# Peripherals.net
KiCad netlist of a schematic drawn in Altium Designer
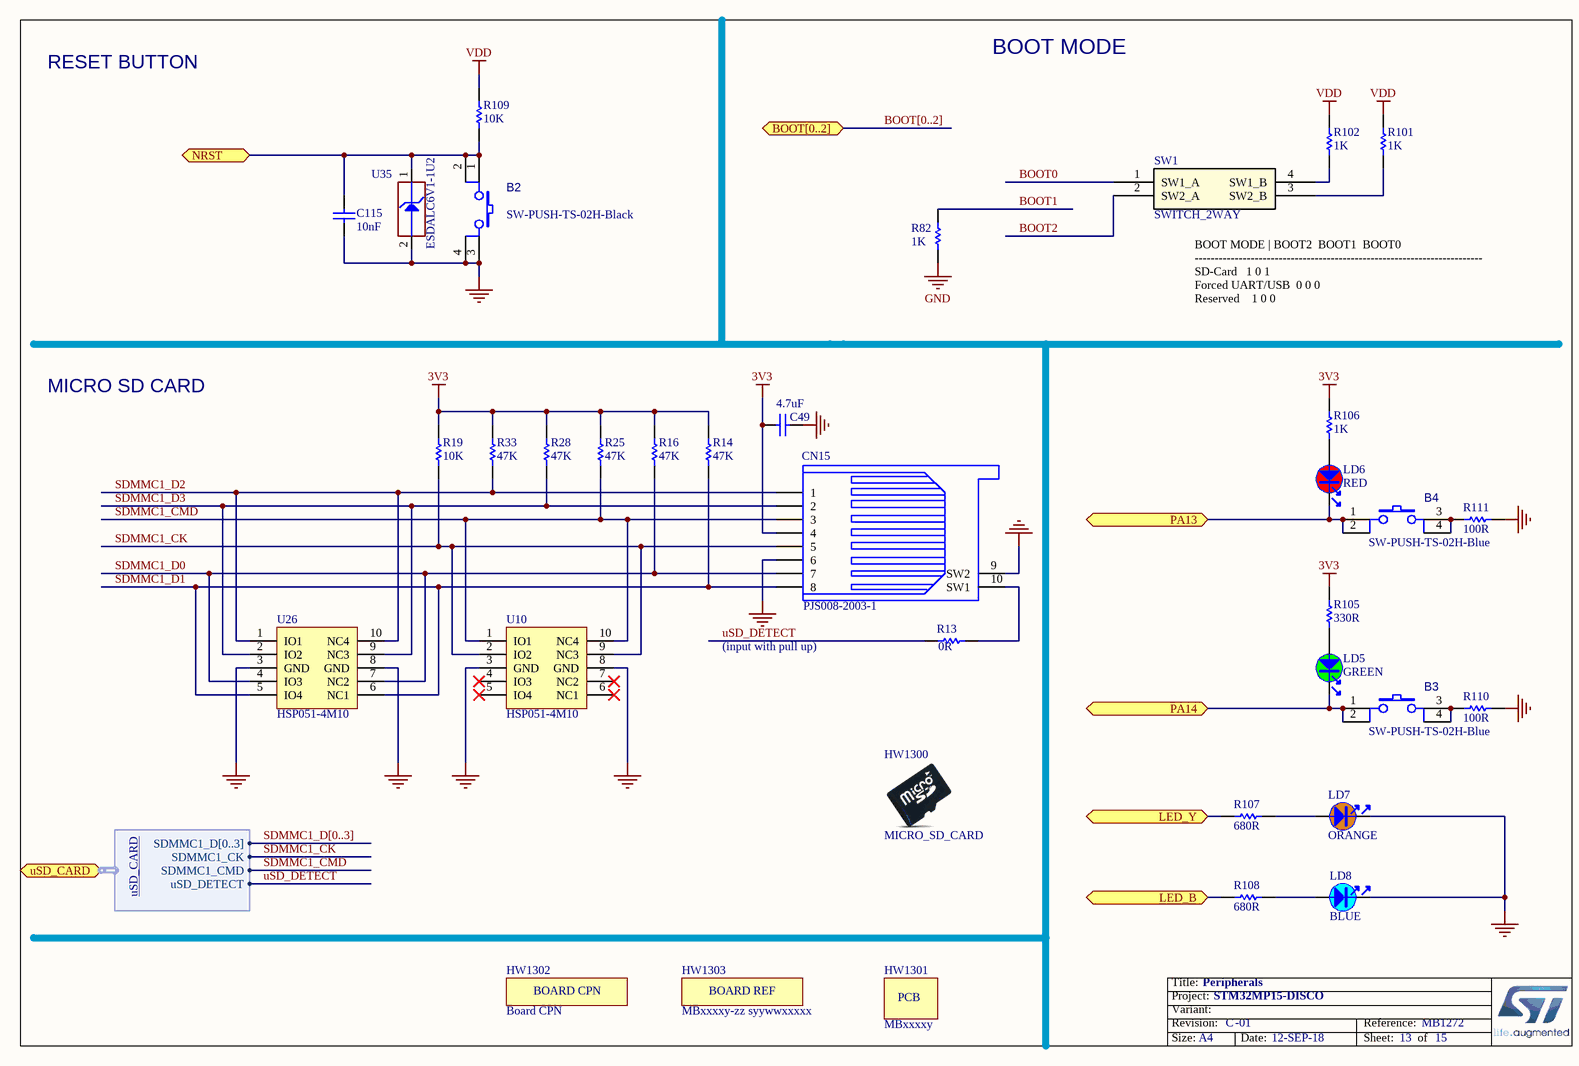
[diagram p0: Peripherals.SchDoc]

(export (version "E")
  (design (tool "Eeschema 10.0.6"))
  (components
    (comp (ref "B2")
      (value "SW-PUSH-TS-02H-Black")
      (footprint "SWI_JIUBABA_C-TS-02H-2-5-K-V-T_R_BLACK")
      (description "Switch HW SMD black")
      (fields
        (field (name "INTERNAL_PART_NUMBER") "MCD-00171")
        (field (name "MANUFACTURER_PART_NUMBER") "C-TS-02H-2.5-K-V-T/R BLACK")
        (field (name "PROVIDED_BY") "SUBCO")
      )
      (libsource (lib "MCD_PARTS_database") (part "SW-PUSH-TS-02H-Black"))
    )
    (comp (ref "B3")
      (value "SW-PUSH-TS-02H-Blue")
      (footprint "SWI_JIUBABA_C-TS-02H-2-5-B-V-T_R_BLUE")
      (description "Switch HW SMD blue")
      (fields
        (field (name "INTERNAL_PART_NUMBER") "MCD-00172")
        (field (name "MANUFACTURER_PART_NUMBER") "C-TS-02H-2.5-B-V-T/R BLUE")
        (field (name "PROVIDED_BY") "SUBCO")
      )
      (libsource (lib "MCD_PARTS_database") (part "SW-PUSH-TS-02H-Blue"))
    )
    (comp (ref "B4")
      (value "SW-PUSH-TS-02H-Blue")
      (footprint "SWI_JIUBABA_C-TS-02H-2-5-B-V-T_R_BLUE")
      (description "Switch HW SMD blue")
      (fields
        (field (name "INTERNAL_PART_NUMBER") "MCD-00172")
        (field (name "MANUFACTURER_PART_NUMBER") "C-TS-02H-2.5-B-V-T/R BLUE")
        (field (name "PROVIDED_BY") "SUBCO")
      )
      (libsource (lib "MCD_PARTS_database") (part "SW-PUSH-TS-02H-Blue"))
    )
    (comp (ref "C49")
      (value "4.7uF")
      (footprint "C0402")
      (description "Capacitor, MLCC, 4.7uF, 6V3, X5R, 20%, 0402, T=0,5mm")
      (fields
        (field (name "INTERNAL_PART_NUMBER") "MCD-01356")
        (field (name "MANUFACTURER_PART_NUMBER") "GRM155R60J475ME47")
        (field (name "PROVIDED_BY") "SUBCO")
      )
      (libsource (lib "MCD_PARTS_database") (part "Capacitor"))
    )
    (comp (ref "C115")
      (value "10nF")
      (footprint "C0402")
      (description "Capacitor, MLCC, 10nF, 16V, X7R, 10%, 0402, T=0.5mm")
      (fields
        (field (name "INTERNAL_PART_NUMBER") "MCD-00011")
        (field (name "MANUFACTURER_PART_NUMBER") "CC0402KRX7R7BB103")
        (field (name "PROVIDED_BY") "SUBCO")
      )
      (libsource (lib "MCD_PARTS_database") (part "Capacitor"))
    )
    (comp (ref "CN15")
      (value "PJS008-2003-1")
      (footprint "CON_MICROSD_YAMAICHI_PJS008-2003-0")
      (description "MicroSD Card Conn, Reversed-Type, Mnt Push-Push")
      (fields
        (field (name "INTERNAL_PART_NUMBER") "MCD-00023")
        (field (name "MANUFACTURER") "YAMAICHI")
        (field (name "PROVIDED_BY") "SUBCO")
      )
      (libsource (lib "MCD_PARTS_database") (part "microSD-PJS008-2003"))
    )
    (comp (ref "HW1300")
      (value "MICRO_SD_CARD")
      (description "MICRO_SD_CARD Standard min 4GB")
      (fields
        (field (name "INTERNAL_PART_NUMBER") "MCD-01200")
        (field (name "MANUFACTURER_PART_NUMBER") "SD_CARD")
        (field (name "PROVIDED_BY") "SUBCO")
      )
      (libsource (lib "MCD_PARTS_database") (part "Micro_SD_card"))
    )
    (comp (ref "HW1301")
      (value "MBxxxxy")
      (description "PCB, xxxx for PCB ref, Y for revision")
      (fields
        (field (name "INTERNAL_PART_NUMBER") "MCD-00216")
        (field (name "MANUFACTURER") "n/a")
        (field (name "PROVIDED_BY") "SUBCO")
      )
      (libsource (lib "MCD_PARTS_database") (part "PCB"))
    )
    (comp (ref "HW1302")
      (value "Board CPN")
      (footprint "STICKER_BOARD-CPN_25X5")
      (description "Sticker to mention board CPN code")
      (fields
        (field (name "INTERNAL_PART_NUMBER") "MCD-00547")
        (field (name "MANUFACTURER_PART_NUMBER") "n/a")
        (field (name "PROVIDED_BY") "SUBCO")
      )
      (libsource (lib "MCD_PARTS_database") (part "STICKER_BOARD_CPN"))
    )
    (comp (ref "HW1303")
      (value "MBxxxxy-zz syywwxxxxx")
      (footprint "STICKER_BOARD-REF_25X5")
      (description "Sticker to mention board reference + serial number")
      (fields
        (field (name "INTERNAL_PART_NUMBER") "MCD-00235")
        (field (name "MANUFACTURER_PART_NUMBER") "n/a")
        (field (name "PROVIDED_BY") "SUBCO")
      )
      (libsource (lib "MCD_PARTS_database") (part "STICKER_BOARD_REF"))
    )
    (comp (ref "LD5")
      (value "GREEN")
      (footprint "LED_0603_GREEN")
      (description "LED, Green, 0603")
      (fields
        (field (name "INTERNAL_PART_NUMBER") "MCD-00050")
        (field (name "MANUFACTURER_PART_NUMBER") "19-213SYGC/S530-E2/TR8")
        (field (name "PROVIDED_BY") "SUBCO")
      )
      (libsource (lib "MCD_PARTS_database") (part "LED_green"))
    )
    (comp (ref "LD6")
      (value "RED")
      (footprint "LED_0603_RED")
      (description "LED, Red, 0603")
      (fields
        (field (name "INTERNAL_PART_NUMBER") "MCD-00049")
        (field (name "MANUFACTURER_PART_NUMBER") "19-213-R6C-AP1Q2B/3T")
        (field (name "PROVIDED_BY") "SUBCO")
      )
      (libsource (lib "MCD_PARTS_database") (part "LED_red"))
    )
    (comp (ref "LD7")
      (value "ORANGE")
      (footprint "LED_0603_ORANGE_H0P4")
      (description "LED, Orange, 0603")
      (fields
        (field (name "INTERNAL_PART_NUMBER") "MCD-00321")
        (field (name "MANUFACTURER_PART_NUMBER") "19-217/S2C-AM2N2VY/3T")
        (field (name "PROVIDED_BY") "SUBCO")
      )
      (libsource (lib "MCD_PARTS_database") (part "LED_orange"))
    )
    (comp (ref "LD8")
      (value "BLUE")
      (footprint "LED_0603_SMD-B_BLUE_H0P4")
      (description "LED Blue, 0603 SMD, Forward Voltage Min=2,8V, Max=3,1V")
      (fields
        (field (name "INTERNAL_PART_NUMBER") "MCD-01131")
        (field (name "MANUFACTURER_PART_NUMBER") "19-217-BHC-ZL1M2RY-3T")
        (field (name "PROVIDED_BY") "SUBCO")
      )
      (libsource (lib "MCD_PARTS_database") (part "LED_blue"))
    )
    (comp (ref "R13")
      (value "0R")
      (footprint "R0402")
      (description "Resistor,0R,0402,5%,1/16W")
      (fields
        (field (name "INTERNAL_PART_NUMBER") "MCD-00052")
        (field (name "MANUFACTURER_PART_NUMBER") "RC0402JR-070RL")
        (field (name "PROVIDED_BY") "SUBCO")
      )
      (libsource (lib "MCD_PARTS_database") (part "Resistor"))
    )
    (comp (ref "R14")
      (value "47K")
      (footprint "R0402")
      (description "Resistor,47K,0402,1%,1/16W")
      (fields
        (field (name "INTERNAL_PART_NUMBER") "MCD-00063")
        (field (name "MANUFACTURER_PART_NUMBER") "RC0402FR-0747KL")
        (field (name "PROVIDED_BY") "SUBCO")
      )
      (libsource (lib "MCD_PARTS_database") (part "Resistor"))
    )
    (comp (ref "R16")
      (value "47K")
      (footprint "R0402")
      (description "Resistor,47K,0402,1%,1/16W")
      (fields
        (field (name "INTERNAL_PART_NUMBER") "MCD-00063")
        (field (name "MANUFACTURER_PART_NUMBER") "RC0402FR-0747KL")
        (field (name "PROVIDED_BY") "SUBCO")
      )
      (libsource (lib "MCD_PARTS_database") (part "Resistor"))
    )
    (comp (ref "R19")
      (value "10K")
      (footprint "R0402")
      (description "Resistor,10K,0402,1%,1/16W")
      (fields
        (field (name "INTERNAL_PART_NUMBER") "MCD-00053")
        (field (name "MANUFACTURER_PART_NUMBER") "RC0402FR-0710KL")
        (field (name "PROVIDED_BY") "SUBCO")
      )
      (libsource (lib "MCD_PARTS_database") (part "Resistor"))
    )
    (comp (ref "R25")
      (value "47K")
      (footprint "R0402")
      (description "Resistor,47K,0402,1%,1/16W")
      (fields
        (field (name "INTERNAL_PART_NUMBER") "MCD-00063")
        (field (name "MANUFACTURER_PART_NUMBER") "RC0402FR-0747KL")
        (field (name "PROVIDED_BY") "SUBCO")
      )
      (libsource (lib "MCD_PARTS_database") (part "Resistor"))
    )
    (comp (ref "R28")
      (value "47K")
      (footprint "R0402")
      (description "Resistor,47K,0402,1%,1/16W")
      (fields
        (field (name "INTERNAL_PART_NUMBER") "MCD-00063")
        (field (name "MANUFACTURER_PART_NUMBER") "RC0402FR-0747KL")
        (field (name "PROVIDED_BY") "SUBCO")
      )
      (libsource (lib "MCD_PARTS_database") (part "Resistor"))
    )
    (comp (ref "R33")
      (value "47K")
      (footprint "R0402")
      (description "Resistor,47K,0402,1%,1/16W")
      (fields
        (field (name "INTERNAL_PART_NUMBER") "MCD-00063")
        (field (name "MANUFACTURER_PART_NUMBER") "RC0402FR-0747KL")
        (field (name "PROVIDED_BY") "SUBCO")
      )
      (libsource (lib "MCD_PARTS_database") (part "Resistor"))
    )
    (comp (ref "R82")
      (value "1K")
      (footprint "R0402")
      (description "Resistor,1K,0402,1%,1/16W")
      (fields
        (field (name "INTERNAL_PART_NUMBER") "MCD-00061")
        (field (name "MANUFACTURER_PART_NUMBER") "RC0402FR-071KL")
        (field (name "PROVIDED_BY") "SUBCO")
      )
      (libsource (lib "MCD_PARTS_database") (part "Resistor"))
    )
    (comp (ref "R101")
      (value "1K")
      (footprint "R0402")
      (description "Resistor,1K,0402,1%,1/16W")
      (fields
        (field (name "INTERNAL_PART_NUMBER") "MCD-00061")
        (field (name "MANUFACTURER_PART_NUMBER") "RC0402FR-071KL")
        (field (name "PROVIDED_BY") "SUBCO")
      )
      (libsource (lib "MCD_PARTS_database") (part "Resistor"))
    )
    (comp (ref "R102")
      (value "1K")
      (footprint "R0402")
      (description "Resistor,1K,0402,1%,1/16W")
      (fields
        (field (name "INTERNAL_PART_NUMBER") "MCD-00061")
        (field (name "MANUFACTURER_PART_NUMBER") "RC0402FR-071KL")
        (field (name "PROVIDED_BY") "SUBCO")
      )
      (libsource (lib "MCD_PARTS_database") (part "Resistor"))
    )
    (comp (ref "R105")
      (value "330R")
      (footprint "R0402")
      (description "Resistor,330R,0402,1%,1/16W")
      (fields
        (field (name "INTERNAL_PART_NUMBER") "MCD-00062")
        (field (name "MANUFACTURER_PART_NUMBER") "RC0402FR-07330RL")
        (field (name "PROVIDED_BY") "SUBCO")
      )
      (libsource (lib "MCD_PARTS_database") (part "Resistor"))
    )
    (comp (ref "R106")
      (value "1K")
      (footprint "R0402")
      (description "Resistor,1K,0402,1%,1/16W")
      (fields
        (field (name "INTERNAL_PART_NUMBER") "MCD-00061")
        (field (name "MANUFACTURER_PART_NUMBER") "RC0402FR-071KL")
        (field (name "PROVIDED_BY") "SUBCO")
      )
      (libsource (lib "MCD_PARTS_database") (part "Resistor"))
    )
    (comp (ref "R107")
      (value "680R")
      (footprint "R0402")
      (description "Resistor,680R,0402,1%,1/16W")
      (fields
        (field (name "INTERNAL_PART_NUMBER") "MCD-00507")
        (field (name "MANUFACTURER_PART_NUMBER") "RC0402FR-07680RL")
        (field (name "PROVIDED_BY") "SUBCO")
      )
      (libsource (lib "MCD_PARTS_database") (part "Resistor"))
    )
    (comp (ref "R108")
      (value "680R")
      (footprint "R0402")
      (description "Resistor,680R,0402,1%,1/16W")
      (fields
        (field (name "INTERNAL_PART_NUMBER") "MCD-00507")
        (field (name "MANUFACTURER_PART_NUMBER") "RC0402FR-07680RL")
        (field (name "PROVIDED_BY") "SUBCO")
      )
      (libsource (lib "MCD_PARTS_database") (part "Resistor"))
    )
    (comp (ref "R109")
      (value "10K")
      (footprint "R0402")
      (description "Resistor,10K,0402,1%,1/16W")
      (fields
        (field (name "INTERNAL_PART_NUMBER") "MCD-00053")
        (field (name "MANUFACTURER_PART_NUMBER") "RC0402FR-0710KL")
        (field (name "PROVIDED_BY") "SUBCO")
      )
      (libsource (lib "MCD_PARTS_database") (part "Resistor"))
    )
    (comp (ref "R110")
      (value "100R")
      (footprint "R0402")
      (description "Resistor,100R,0402,1%,1/16W")
      (fields
        (field (name "INTERNAL_PART_NUMBER") "MCD-00067")
        (field (name "MANUFACTURER_PART_NUMBER") "RC0402FR-07100RL")
        (field (name "PROVIDED_BY") "SUBCO")
      )
      (libsource (lib "MCD_PARTS_database") (part "Resistor"))
    )
    (comp (ref "R111")
      (value "100R")
      (footprint "R0402")
      (description "Resistor,100R,0402,1%,1/16W")
      (fields
        (field (name "INTERNAL_PART_NUMBER") "MCD-00067")
        (field (name "MANUFACTURER_PART_NUMBER") "RC0402FR-07100RL")
        (field (name "PROVIDED_BY") "SUBCO")
      )
      (libsource (lib "MCD_PARTS_database") (part "Resistor"))
    )
    (comp (ref "SW1")
      (value "SWITCH_2WAY")
      (footprint "SWI_C&K_SDA02H1SBD_2POS")
      (description "Dip Switch ,2Position ,Surface Mount Slide (Standard) ,2.54 pitch,25mA 24VDC")
      (fields
        (field (name "INTERNAL_PART_NUMBER") "MCD-00658")
        (field (name "MANUFACTURER_PART_NUMBER") "SDA02H1SBD")
        (field (name "PROVIDED_BY") "SUBCO")
      )
      (libsource (lib "MCD_PARTS_database") (part "SWITCH_2WAY"))
    )
    (comp (ref "U10")
      (value "HSP051-4M10")
      (footprint "ESD_UQFN-10L_2P5X1_P050")
      (description "4-line ESD protection for high speed lines")
      (fields
        (field (name "INTERNAL_PART_NUMBER") "MCD-00667")
        (field (name "MANUFACTURER") "STMICROELECTRONICS")
        (field (name "PROVIDED_BY") "SUBCO with ST control")
      )
      (libsource (lib "MCD_PARTS_database") (part "HSP051-4M10"))
    )
    (comp (ref "U26")
      (value "HSP051-4M10")
      (footprint "ESD_UQFN-10L_2P5X1_P050")
      (description "4-line ESD protection for high speed lines")
      (fields
        (field (name "INTERNAL_PART_NUMBER") "MCD-00667")
        (field (name "MANUFACTURER") "STMICROELECTRONICS")
        (field (name "PROVIDED_BY") "SUBCO with ST control")
      )
      (libsource (lib "MCD_PARTS_database") (part "HSP051-4M10"))
    )
    (comp (ref "U35")
      (value "ESDALC6V1-1U2")
      (footprint "ESD_ST0201")
      (description "ESD protection 6V1")
      (fields
        (field (name "INTERNAL_PART_NUMBER") "MCD-00170")
        (field (name "MANUFACTURER") "STMICROELECTRONICS")
        (field (name "PROVIDED_BY") "SUBCO with ST control")
      )
      (libsource (lib "MCD_PARTS_database") (part "ESD-TRANSIL"))
    )
  )
  (nets
    (net (code "2") (name "/BOOT0") (class "Default")
      (node (ref "SW1") (pin "1") (pinfunction "SW1_A_1") (pintype "passive"))
    )
    (net (code "3") (name "/BOOT1") (class "Default")
      (node (ref "R82") (pin "2") (pinfunction "2_2") (pintype "passive"))
    )
    (net (code "4") (name "/BOOT2") (class "Default")
      (node (ref "SW1") (pin "2") (pinfunction "SW2_A_2") (pintype "passive"))
    )
    (net (code "6") (name "/LED_B") (class "Default")
      (node (ref "R108") (pin "1") (pinfunction "1_1") (pintype "passive"))
    )
    (net (code "7") (name "/LED_Y") (class "Default")
      (node (ref "R107") (pin "1") (pinfunction "1_1") (pintype "passive"))
    )
    (net (code "8") (name "/NRST") (class "Default")
      (node (ref "B2") (pin "1") (pinfunction "1_1") (pintype "passive"))
      (node (ref "B2") (pin "2") (pinfunction "2_2") (pintype "passive"))
      (node (ref "C115") (pin "2") (pinfunction "2_2") (pintype "passive"))
      (node (ref "R109") (pin "1") (pinfunction "1_1") (pintype "passive"))
      (node (ref "U35") (pin "1") (pinfunction "IO1_1") (pintype "passive"))
    )
    (net (code "9") (name "/PA13") (class "Default")
      (node (ref "B4") (pin "1") (pinfunction "1_1") (pintype "passive"))
      (node (ref "B4") (pin "2") (pinfunction "2_2") (pintype "passive"))
      (node (ref "LD6") (pin "2") (pintype "passive"))
    )
    (net (code "10") (name "/PA14") (class "Default")
      (node (ref "B3") (pin "1") (pinfunction "1_1") (pintype "passive"))
      (node (ref "B3") (pin "2") (pinfunction "2_2") (pintype "passive"))
      (node (ref "LD5") (pin "2") (pintype "passive"))
    )
    (net (code "11") (name "/SDMMC1_CK") (class "Default")
      (node (ref "CN15") (pin "5") (pinfunction "5_5") (pintype "passive"))
      (node (ref "R19") (pin "1") (pinfunction "1_1") (pintype "passive"))
      (node (ref "U10") (pin "2") (pinfunction "IO2_2") (pintype "passive"))
      (node (ref "U10") (pin "9") (pinfunction "NC3_9") (pintype "passive"))
    )
    (net (code "12") (name "/SDMMC1_CMD") (class "Default")
      (node (ref "CN15") (pin "3") (pinfunction "3_3") (pintype "passive"))
      (node (ref "R25") (pin "1") (pinfunction "1_1") (pintype "passive"))
      (node (ref "U10") (pin "1") (pinfunction "IO1_1") (pintype "passive"))
      (node (ref "U10") (pin "10") (pinfunction "NC4_10") (pintype "passive"))
    )
    (net (code "13") (name "/SDMMC1_D0") (class "Default")
      (node (ref "CN15") (pin "7") (pinfunction "7_7") (pintype "passive"))
      (node (ref "R16") (pin "1") (pinfunction "1_1") (pintype "passive"))
      (node (ref "U26") (pin "4") (pinfunction "IO3_4") (pintype "passive"))
      (node (ref "U26") (pin "7") (pinfunction "NC2_7") (pintype "passive"))
    )
    (net (code "14") (name "/SDMMC1_D1") (class "Default")
      (node (ref "CN15") (pin "8") (pinfunction "8_8") (pintype "passive"))
      (node (ref "R14") (pin "1") (pinfunction "1_1") (pintype "passive"))
      (node (ref "U26") (pin "5") (pinfunction "IO4_5") (pintype "passive"))
      (node (ref "U26") (pin "6") (pinfunction "NC1_6") (pintype "passive"))
    )
    (net (code "15") (name "/SDMMC1_D2") (class "Default")
      (node (ref "CN15") (pin "1") (pinfunction "1_1") (pintype "passive"))
      (node (ref "R33") (pin "1") (pinfunction "1_1") (pintype "passive"))
      (node (ref "U26") (pin "1") (pinfunction "IO1_1") (pintype "passive"))
      (node (ref "U26") (pin "10") (pinfunction "NC4_10") (pintype "passive"))
    )
    (net (code "16") (name "/SDMMC1_D3") (class "Default")
      (node (ref "CN15") (pin "2") (pinfunction "2_2") (pintype "passive"))
      (node (ref "R28") (pin "1") (pinfunction "1_1") (pintype "passive"))
      (node (ref "U26") (pin "2") (pinfunction "IO2_2") (pintype "passive"))
      (node (ref "U26") (pin "9") (pinfunction "NC3_9") (pintype "passive"))
    )
    (net (code "18") (name "/uSD_DETECT") (class "Default")
      (node (ref "R13") (pin "1") (pinfunction "1_1") (pintype "passive"))
    )
    (net (code "20") (name "3V3") (class "Default")
      (node (ref "C49") (pin "2") (pinfunction "2_2") (pintype "passive"))
      (node (ref "CN15") (pin "4") (pinfunction "4_4") (pintype "passive"))
      (node (ref "R105") (pin "2") (pinfunction "2_2") (pintype "passive"))
      (node (ref "R106") (pin "2") (pinfunction "2_2") (pintype "passive"))
      (node (ref "R14") (pin "2") (pinfunction "2_2") (pintype "passive"))
      (node (ref "R16") (pin "2") (pinfunction "2_2") (pintype "passive"))
      (node (ref "R19") (pin "2") (pinfunction "2_2") (pintype "passive"))
      (node (ref "R25") (pin "2") (pinfunction "2_2") (pintype "passive"))
      (node (ref "R28") (pin "2") (pinfunction "2_2") (pintype "passive"))
      (node (ref "R33") (pin "2") (pinfunction "2_2") (pintype "passive"))
    )
    (net (code "21") (name "GND") (class "Default")
      (node (ref "B2") (pin "3") (pinfunction "3_3") (pintype "passive"))
      (node (ref "B2") (pin "4") (pinfunction "4_4") (pintype "passive"))
      (node (ref "C115") (pin "1") (pinfunction "1_1") (pintype "passive"))
      (node (ref "C49") (pin "1") (pinfunction "1_1") (pintype "passive"))
      (node (ref "CN15") (pin "6") (pinfunction "6_6") (pintype "passive"))
      (node (ref "CN15") (pin "9") (pinfunction "SW2_9") (pintype "passive"))
      (node (ref "LD7") (pin "2") (pintype "passive"))
      (node (ref "LD8") (pin "2") (pintype "passive"))
      (node (ref "R110") (pin "2") (pinfunction "2_2") (pintype "passive"))
      (node (ref "R111") (pin "2") (pinfunction "2_2") (pintype "passive"))
      (node (ref "R82") (pin "1") (pinfunction "1_1") (pintype "passive"))
      (node (ref "U10") (pin "3") (pinfunction "GND_3") (pintype "passive"))
      (node (ref "U10") (pin "8") (pinfunction "GND_8") (pintype "passive"))
      (node (ref "U26") (pin "3") (pinfunction "GND_3") (pintype "passive"))
      (node (ref "U26") (pin "8") (pinfunction "GND_8") (pintype "passive"))
      (node (ref "U35") (pin "2") (pinfunction "GND_2") (pintype "passive"))
    )
    (net (code "22") (name "Net-(B3-Pad3)") (class "Default")
      (node (ref "B3") (pin "3") (pinfunction "3_3") (pintype "passive"))
      (node (ref "B3") (pin "4") (pinfunction "4_4") (pintype "passive"))
      (node (ref "R110") (pin "1") (pinfunction "1_1") (pintype "passive"))
    )
    (net (code "23") (name "Net-(B4-Pad3)") (class "Default")
      (node (ref "B4") (pin "3") (pinfunction "3_3") (pintype "passive"))
      (node (ref "B4") (pin "4") (pinfunction "4_4") (pintype "passive"))
      (node (ref "R111") (pin "1") (pinfunction "1_1") (pintype "passive"))
    )
    (net (code "24") (name "Net-(CN15-SW1)") (class "Default")
      (node (ref "CN15") (pin "10") (pinfunction "SW1_10") (pintype "passive"))
      (node (ref "R13") (pin "2") (pinfunction "2_2") (pintype "passive"))
    )
    (net (code "25") (name "Net-(LD5-Pad1)") (class "Default")
      (node (ref "LD5") (pin "1") (pintype "passive"))
      (node (ref "R105") (pin "1") (pinfunction "1_1") (pintype "passive"))
    )
    (net (code "26") (name "Net-(LD6-Pad1)") (class "Default")
      (node (ref "LD6") (pin "1") (pintype "passive"))
      (node (ref "R106") (pin "1") (pinfunction "1_1") (pintype "passive"))
    )
    (net (code "27") (name "Net-(LD7-Pad1)") (class "Default")
      (node (ref "LD7") (pin "1") (pintype "passive"))
      (node (ref "R107") (pin "2") (pinfunction "2_2") (pintype "passive"))
    )
    (net (code "28") (name "Net-(LD8-Pad1)") (class "Default")
      (node (ref "LD8") (pin "1") (pintype "passive"))
      (node (ref "R108") (pin "2") (pinfunction "2_2") (pintype "passive"))
    )
    (net (code "29") (name "Net-(SW1-SW1_B)") (class "Default")
      (node (ref "R102") (pin "1") (pinfunction "1_1") (pintype "passive"))
      (node (ref "SW1") (pin "4") (pinfunction "SW1_B_4") (pintype "passive"))
    )
    (net (code "30") (name "Net-(SW1-SW2_B)") (class "Default")
      (node (ref "R101") (pin "1") (pinfunction "1_1") (pintype "passive"))
      (node (ref "SW1") (pin "3") (pinfunction "SW2_B_3") (pintype "passive"))
    )
    (net (code "31") (name "VDD") (class "Default")
      (node (ref "R101") (pin "2") (pinfunction "2_2") (pintype "passive"))
      (node (ref "R102") (pin "2") (pinfunction "2_2") (pintype "passive"))
      (node (ref "R109") (pin "2") (pinfunction "2_2") (pintype "passive"))
    )
    (net (code "32") (name "unconnected-(U10-IO3-Pad4)") (class "Default")
      (node (ref "U10") (pin "4") (pinfunction "IO3_4") (pintype "passive+no_connect"))
    )
    (net (code "33") (name "unconnected-(U10-IO4-Pad5)") (class "Default")
      (node (ref "U10") (pin "5") (pinfunction "IO4_5") (pintype "passive+no_connect"))
    )
    (net (code "34") (name "unconnected-(U10-NC1-Pad6)") (class "Default")
      (node (ref "U10") (pin "6") (pinfunction "NC1_6") (pintype "passive+no_connect"))
    )
    (net (code "35") (name "unconnected-(U10-NC2-Pad7)") (class "Default")
      (node (ref "U10") (pin "7") (pinfunction "NC2_7") (pintype "passive+no_connect"))
    )
  )
)
